# DM1098OAKW_Power_Supply.net
KiCad netlist of a schematic drawn in Altium Designer
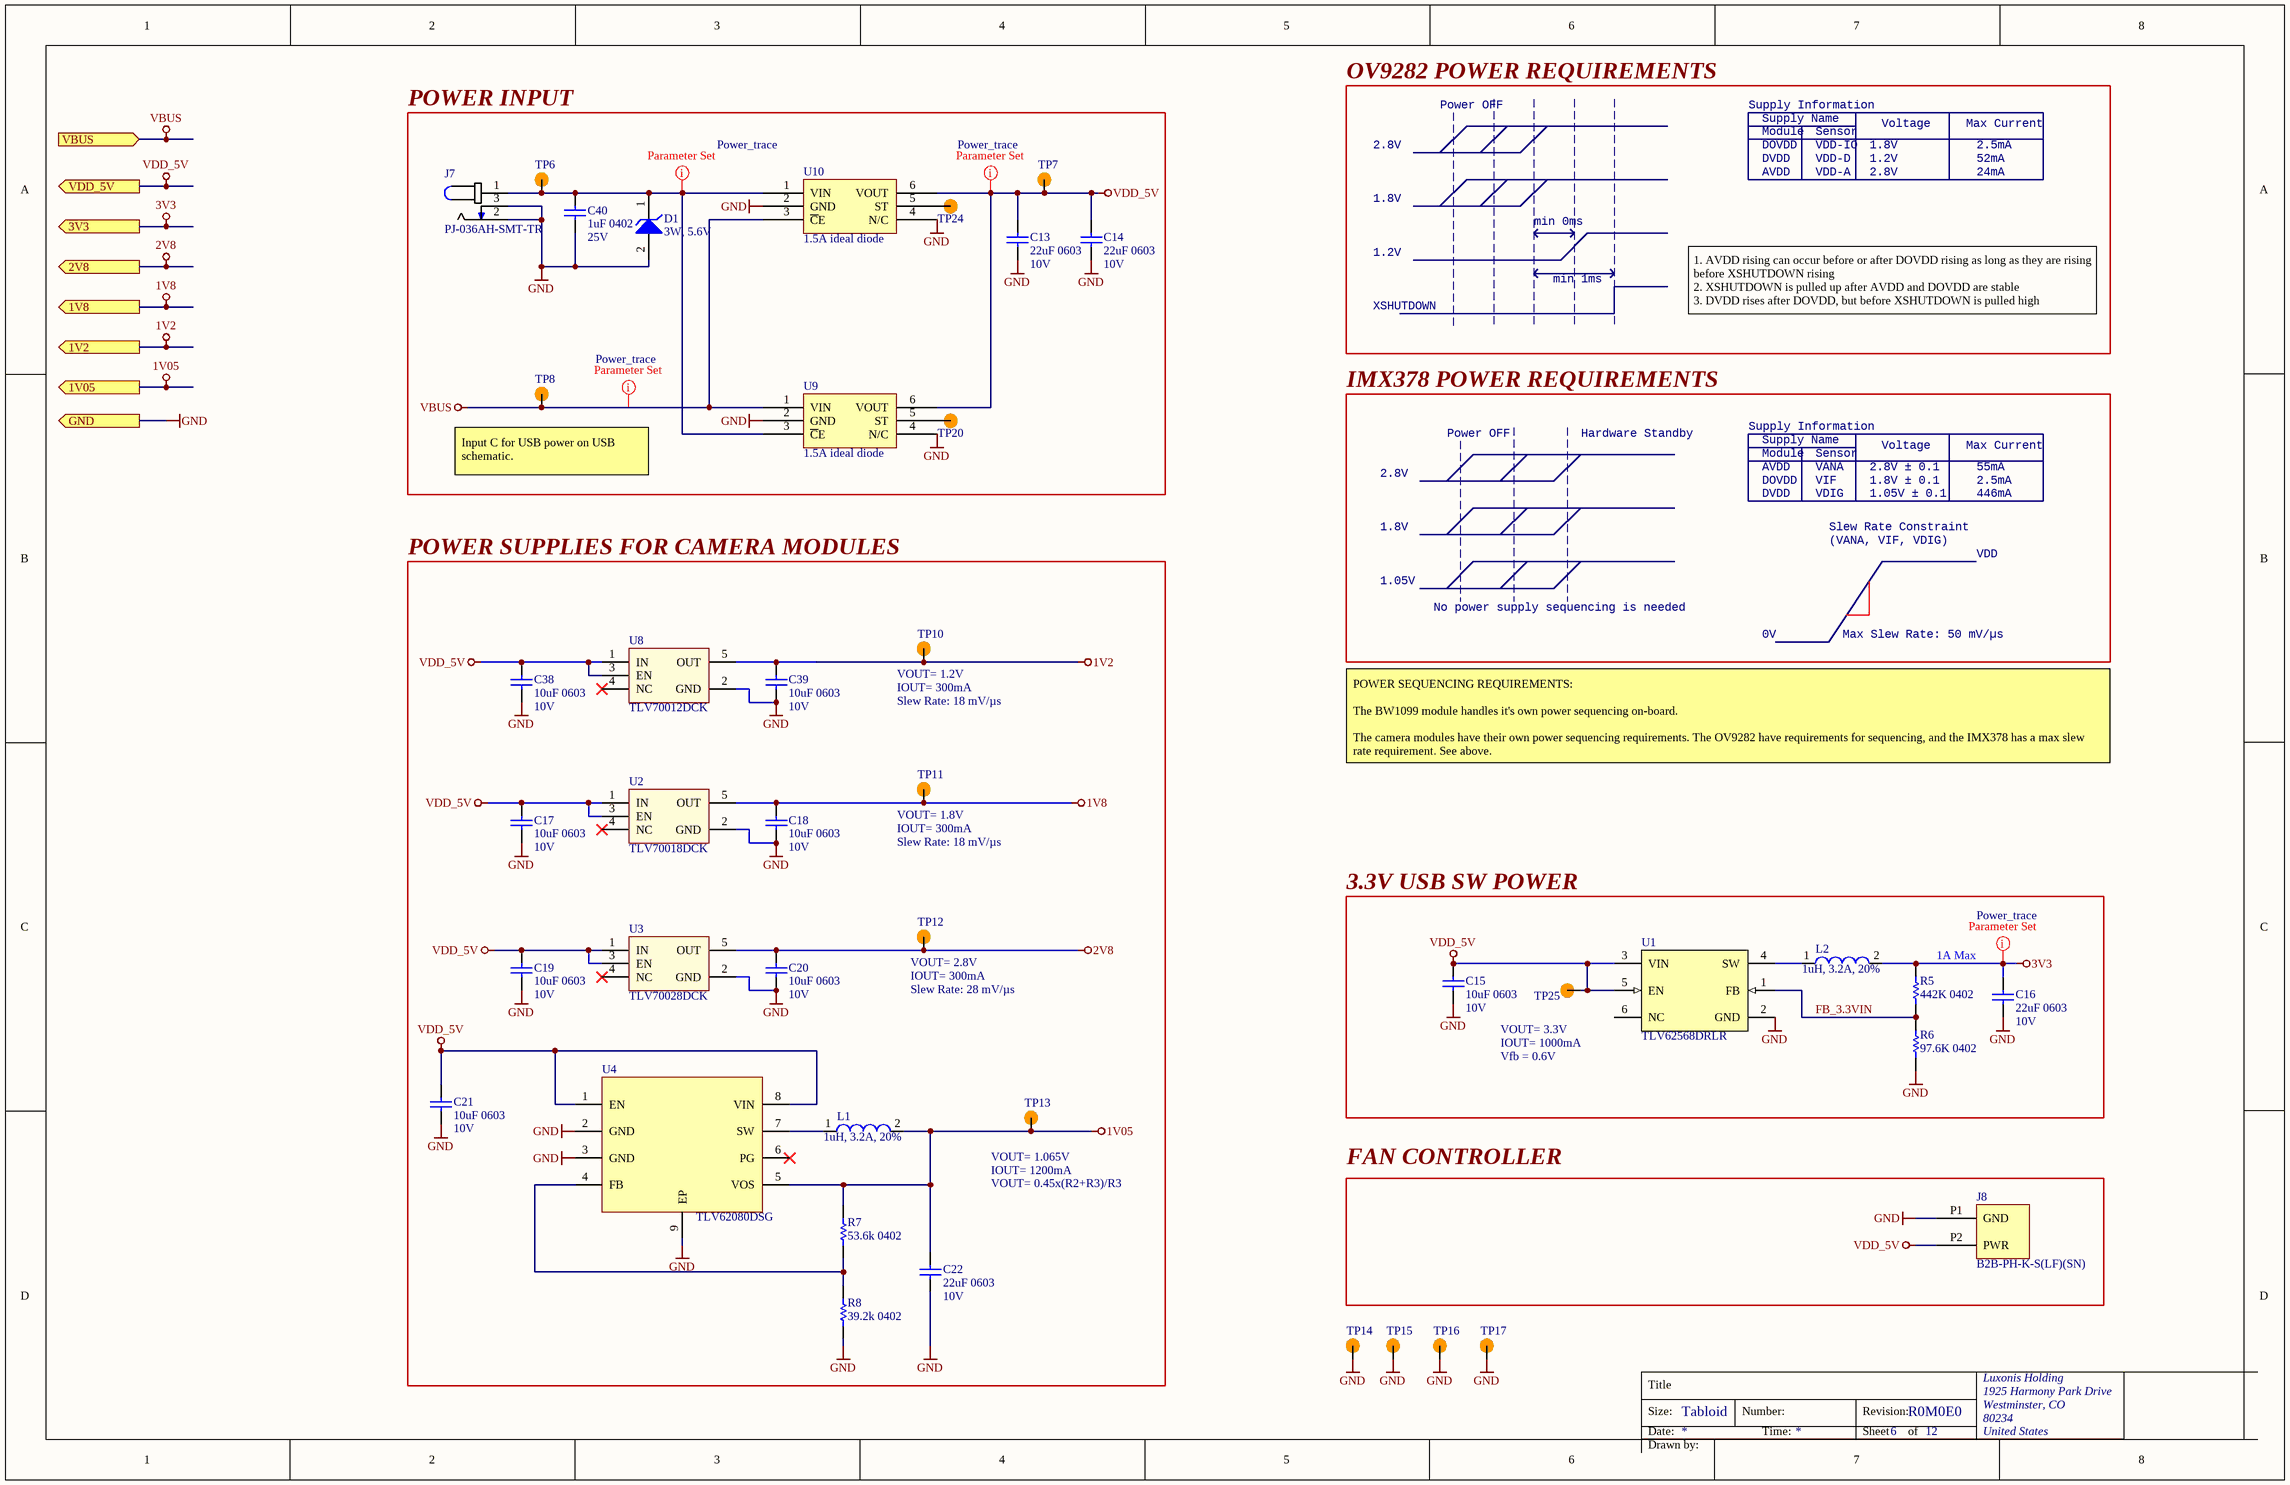
[diagram p0: DM1098OAKW_Power_Supply.SchDoc]

(export (version "E")
  (design (tool "Eeschema 10.0.6"))
  (components
    (comp (ref "C13")
      (value "22uF 0603")
      (footprint "CAP_Altium_Vault_Generic:CAPC0603(1608)100_L")
      (description "CAP CER 22UF 10V X5R 0603 20%")
      (fields (field (name "TOLERANCE") "20%") (field (name "VOLTAGE RATING") "10V"))
      (libsource (lib "LuxonisMaster") (part "GRM188R61A226ME15D"))
    )
    (comp (ref "C14")
      (value "22uF 0603")
      (footprint "CAP_Altium_Vault_Generic:CAPC0603(1608)100_L")
      (description "CAP CER 22UF 10V X5R 0603 20%")
      (fields (field (name "TOLERANCE") "20%") (field (name "VOLTAGE RATING") "10V"))
      (libsource (lib "LuxonisMaster") (part "GRM188R61A226ME15D"))
    )
    (comp (ref "C15")
      (value "10uF 0603")
      (footprint "CAP_Altium_Vault_Generic:CAPC0603(1608)100_L")
      (description "CAP CER 10UF 10V X5R 0603 20%")
      (fields (field (name "TOLERANCE") "20%") (field (name "VOLTAGE RATING") "10V"))
      (libsource (lib "LuxonisMaster") (part "GRM188R61A106ME69D"))
    )
    (comp (ref "C16")
      (value "22uF 0603")
      (footprint "CAP_Altium_Vault_Generic:CAPC0603(1608)100_N")
      (description "CAP CER 22UF 10V X5R 0603 20%")
      (fields (field (name "TOLERANCE") "20%") (field (name "VOLTAGE RATING") "10V"))
      (libsource (lib "LuxonisMaster") (part "GRM188R61A226ME15D"))
    )
    (comp (ref "C17")
      (value "10uF 0603")
      (footprint "CAP_Altium_Vault_Generic:CAPC0603(1608)100_L")
      (description "CAP CER 10UF 10V X5R 0603 20%")
      (fields (field (name "TOLERANCE") "20%") (field (name "VOLTAGE RATING") "10V"))
      (libsource (lib "LuxonisMaster") (part "GRM188R61A106ME69D"))
    )
    (comp (ref "C18")
      (value "10uF 0603")
      (footprint "CAP_Altium_Vault_Generic:CAPC0603(1608)100_L")
      (description "CAP CER 10UF 10V X5R 0603 20%")
      (fields (field (name "TOLERANCE") "20%") (field (name "VOLTAGE RATING") "10V"))
      (libsource (lib "LuxonisMaster") (part "GRM188R61A106ME69D"))
    )
    (comp (ref "C19")
      (value "10uF 0603")
      (footprint "CAP_Altium_Vault_Generic:CAPC0603(1608)100_L")
      (description "CAP CER 10UF 10V X5R 0603 20%")
      (fields (field (name "TOLERANCE") "20%") (field (name "VOLTAGE RATING") "10V"))
      (libsource (lib "LuxonisMaster") (part "GRM188R61A106ME69D"))
    )
    (comp (ref "C20")
      (value "10uF 0603")
      (footprint "CAP_Altium_Vault_Generic:CAPC0603(1608)100_L")
      (description "CAP CER 10UF 10V X5R 0603 20%")
      (fields (field (name "TOLERANCE") "20%") (field (name "VOLTAGE RATING") "10V"))
      (libsource (lib "LuxonisMaster") (part "GRM188R61A106ME69D"))
    )
    (comp (ref "C21")
      (value "10uF 0603")
      (footprint "CAP_Altium_Vault_Generic:CAPC0603(1608)100_L")
      (description "CAP CER 10UF 10V X5R 0603 20%")
      (fields (field (name "TOLERANCE") "20%") (field (name "VOLTAGE RATING") "10V"))
      (libsource (lib "LuxonisMaster") (part "GRM188R61A106ME69D"))
    )
    (comp (ref "C22")
      (value "22uF 0603")
      (footprint "CAP_Altium_Vault_Generic:CAPC0603(1608)100_L")
      (description "CAP CER 22UF 10V X5R 0603 20%")
      (fields (field (name "TOLERANCE") "20%") (field (name "VOLTAGE RATING") "10V"))
      (libsource (lib "LuxonisMaster") (part "GRM188R61A226ME15D"))
    )
    (comp (ref "C38")
      (value "10uF 0603")
      (footprint "CAP_Altium_Vault_Generic:CAPC0603(1608)100_L")
      (description "CAP CER 10UF 10V X5R 0603 20%")
      (fields (field (name "TOLERANCE") "20%") (field (name "VOLTAGE RATING") "10V"))
      (libsource (lib "LuxonisMaster") (part "GRM188R61A106ME69D"))
    )
    (comp (ref "C39")
      (value "10uF 0603")
      (footprint "CAP_Altium_Vault_Generic:CAPC0603(1608)100_L")
      (description "CAP CER 10UF 10V X5R 0603 20%")
      (fields (field (name "TOLERANCE") "20%") (field (name "VOLTAGE RATING") "10V"))
      (libsource (lib "LuxonisMaster") (part "GRM188R61A106ME69D"))
    )
    (comp (ref "C40")
      (value "1uF 0402")
      (footprint "CAP_Altium_Vault_Generic:CAPC0402(1005)70_L")
      (description "CAP CER 1UF 25V X5R 0402 10%")
      (fields
        (field (name "TOLERANCE") "10%")
        (field (name "VOLTAGE") "25V")
        (field (name "VOLTAGE RATING") "25V")
      )
      (libsource (lib "LuxonisMaster") (part "GRM155R61E105KA12D"))
    )
    (comp (ref "D1")
      (value "3W, 5.6V")
      (footprint "DM1092_R0M0E0:1SMB5919BT3G")
      (description "DIODE ZENER 5.6V 3W SMB")
      (fields (field (name "TOLERANCE") "5%"))
      (libsource (lib "DM1092_R0M0E0") (part "1SMB5919BT3G"))
    )
    (comp (ref "J7")
      (value "PJ-036AH-SMT-TR")
      (footprint "LuxonisMaster:PJ-036AH-SMT")
      (description "CONN PWR JACK 2X5.5MM SOLDER")
      (libsource (lib "LuxonisMaster") (part "PJ-036AH-SMT-TR"))
    )
    (comp (ref "J8")
      (value "B2B-PH-K-S(LF)(SN)")
      (footprint "LuxonisMaster:B2B-PH-K-S(LF)(SN)")
      (description "CONN HEADER VERT 2POS 2MM")
      (fields (field (name "MANUFACTURER") "JST"))
      (libsource (lib "LuxonisMaster") (part "B2B-PH-K-S(LF)(SN)"))
    )
    (comp (ref "L1")
      (value "1uH, 3.2A, 20%")
      (footprint "LuxonisMaster:DFE252012P-1R0M=P2")
      (description "FIXED IND 1UH 3.2A 42 MOHM SMD")
      (fields
        (field (name "MANUFACTURER") "Murata")
        (field (name "MANUFACTURER PART NUMBER") "DFE252012P-1R0M=P2")
      )
      (libsource (lib "LuxonisMaster") (part "DFE252012P-1R0M=P2"))
    )
    (comp (ref "L2")
      (value "1uH, 3.2A, 20%")
      (footprint "LuxonisMaster:DFE252012P-1R0M=P2")
      (description "FIXED IND 1UH 3.2A 42 MOHM SMD")
      (fields
        (field (name "MANUFACTURER") "Murata")
        (field (name "MANUFACTURER PART NUMBER") "DFE252012P-1R0M=P2")
      )
      (libsource (lib "LuxonisMaster") (part "DFE252012P-1R0M=P2"))
    )
    (comp (ref "R5")
      (value "442K 0402")
      (footprint "RES_Altium_Vault_Generic:RESC0402(1005)_N")
      (description "RES SMD 442K OHM 1% 1/16W 0402")
      (fields (field (name "TOLERANCE") "1%"))
      (libsource (lib "BW1092_R0M0E0") (part "CRCW0402442KFKED"))
    )
    (comp (ref "R6")
      (value "97.6K 0402")
      (footprint "RES_Altium_Vault_Generic:RESC0402(1005)_N")
      (description "RES SMD 97.6K OHM 1% 1/16W 0402")
      (fields (field (name "TOLERANCE") "1%"))
      (libsource (lib "BW1092_R0M0E0") (part "CRCW040297K6FKED"))
    )
    (comp (ref "R7")
      (value "53.6k 0402")
      (footprint "RES_Altium_Vault_Generic:RESC0402(1005)_L")
      (description "RES SMD 53.6K OHM 1% 1/16W 0402")
      (fields (field (name "TOLERANCE") "1%"))
      (libsource (lib "LuxonisMaster") (part "CRCW040253K6FKED"))
    )
    (comp (ref "R8")
      (value "39.2k 0402")
      (footprint "RES_Altium_Vault_Generic:RESC0402(1005)_L")
      (description "RES SMD 39.2K OHM 1% 1/16W 0402")
      (fields (field (name "TOLERANCE") "1%"))
      (libsource (lib "LuxonisMaster") (part "CRCW040239K2FKED"))
    )
    (comp (ref "TP6")
      (value "TP100_200_NS")
      (footprint "LuxonisMaster:TP100_200_NS")
      (libsource (lib "LuxonisMaster") (part "TEST_POINT"))
    )
    (comp (ref "TP7")
      (value "TP100_200_NS")
      (footprint "LuxonisMaster:TP100_200_NS")
      (libsource (lib "LuxonisMaster") (part "TEST_POINT"))
    )
    (comp (ref "TP8")
      (value "TP100_200_NS")
      (footprint "LuxonisMaster:TP100_200_NS")
      (libsource (lib "LuxonisMaster") (part "TEST_POINT"))
    )
    (comp (ref "TP10")
      (value "TP100_200_NS")
      (footprint "LuxonisMaster:TP100_200_NS")
      (libsource (lib "LuxonisMaster") (part "TEST_POINT"))
    )
    (comp (ref "TP11")
      (value "TP100_200_NS")
      (footprint "LuxonisMaster:TP100_200_NS")
      (libsource (lib "LuxonisMaster") (part "TEST_POINT"))
    )
    (comp (ref "TP12")
      (value "TP100_200_NS")
      (footprint "LuxonisMaster:TP100_200_NS")
      (libsource (lib "LuxonisMaster") (part "TEST_POINT"))
    )
    (comp (ref "TP13")
      (value "TP100_200_NS")
      (footprint "LuxonisMaster:TP100_200_NS")
      (libsource (lib "LuxonisMaster") (part "TEST_POINT"))
    )
    (comp (ref "TP14")
      (value "TP100_200_NS")
      (footprint "LuxonisMaster:TP100_200_NS")
      (libsource (lib "LuxonisMaster") (part "TEST_POINT"))
    )
    (comp (ref "TP15")
      (value "TP100_200_NS")
      (footprint "LuxonisMaster:TP100_200_NS")
      (libsource (lib "LuxonisMaster") (part "TEST_POINT"))
    )
    (comp (ref "TP16")
      (value "TP100_200_NS")
      (footprint "LuxonisMaster:TP100_200_NS")
      (libsource (lib "LuxonisMaster") (part "TEST_POINT"))
    )
    (comp (ref "TP17")
      (value "TP100_200_NS")
      (footprint "LuxonisMaster:TP100_200_NS")
      (libsource (lib "LuxonisMaster") (part "TEST_POINT"))
    )
    (comp (ref "TP20")
      (value "TP100_200_NS")
      (footprint "LuxonisMaster:TP100_200_NS")
      (libsource (lib "LuxonisMaster") (part "TEST_POINT"))
    )
    (comp (ref "TP24")
      (value "TP100_200_NS")
      (footprint "LuxonisMaster:TP100_200_NS")
      (libsource (lib "LuxonisMaster") (part "TEST_POINT"))
    )
    (comp (ref "TP25")
      (value "TP100_200_NS")
      (footprint "LuxonisMaster:TP100_200_NS")
      (libsource (lib "LuxonisMaster") (part "TEST_POINT"))
    )
    (comp (ref "U1")
      (value "TLV62568DRLR")
      (footprint "BW1092_R0M0E0:TLV62568DRLR")
      (description "IC REG BUCK ADJ 1A SOT563-6")
      (libsource (lib "BW1092_R0M0E0") (part "TLV62568DRLR"))
    )
    (comp (ref "U2")
      (value "TLV70018DCK")
      (footprint "LuxonisMaster:TLV70018DCK")
      (description "IC REG LINEAR 1.8V 200MA SC70-5 Linear Voltage Regulator IC  1 Output  200mA SC-70-5")
      (libsource (lib "LuxonisMaster") (part "TLV70018DCK"))
    )
    (comp (ref "U3")
      (value "TLV70028DCK")
      (footprint "LuxonisMaster:TLV70028DCK")
      (description "IC REG LINEAR 2.8V 200MA SC70-5 Linear Voltage Regulator IC  1 Output  200mA SC-70-5")
      (libsource (lib "LuxonisMaster") (part "TLV70028DCK"))
    )
    (comp (ref "U4")
      (value "TLV62080DSG")
      (footprint "LuxonisMaster:TLV62080DSG")
      (description "IC REG BUCK ADJ 1.2A SYNC 8WSON")
      (libsource (lib "LuxonisMaster") (part "TLV62080DSG"))
    )
    (comp (ref "U8")
      (value "TLV70012DCK")
      (footprint "LuxonisMaster:TLV70012DCK")
      (description "IC REG LINEAR 1.2V 200MA SC70-5")
      (libsource (lib "LuxonisMaster") (part "TLV70012DCK"))
    )
    (comp (ref "U9")
      (value "1.5A ideal diode")
      (footprint "BW1098OBC_R2M0E2:LM66100DCKR")
      (description "IC OR CTRLR IDEAL DIODE SC70-6")
      (libsource (lib "BW1098OBC_R2M0E2") (part "LM66100DCKR"))
    )
    (comp (ref "U10")
      (value "1.5A ideal diode")
      (footprint "BW1098OBC_R2M0E2:LM66100DCKR")
      (description "IC OR CTRLR IDEAL DIODE SC70-6")
      (libsource (lib "BW1098OBC_R2M0E2") (part "LM66100DCKR"))
    )
  )
  (nets
    (net (code "1") (name "/FB_3.3VIN") (class "Default")
      (node (ref "R5") (pin "1") (pinfunction "1_1") (pintype "passive"))
      (node (ref "R6") (pin "2") (pinfunction "2_2") (pintype "passive"))
      (node (ref "U1") (pin "1") (pinfunction "FB_1") (pintype "input"))
    )
    (net (code "2") (name "1V2") (class "Default")
      (node (ref "C39") (pin "2") (pinfunction "2_2") (pintype "passive"))
      (node (ref "TP10") (pin "1") (pintype "passive"))
      (node (ref "U8") (pin "5") (pinfunction "OUT_5") (pintype "passive"))
    )
    (net (code "3") (name "1V05") (class "Default")
      (node (ref "C22") (pin "2") (pinfunction "2_2") (pintype "passive"))
      (node (ref "L1") (pin "2") (pinfunction "2_2") (pintype "passive"))
      (node (ref "R7") (pin "2") (pinfunction "2_2") (pintype "passive"))
      (node (ref "TP13") (pin "1") (pintype "passive"))
      (node (ref "U4") (pin "5") (pinfunction "VOS_5") (pintype "passive"))
    )
    (net (code "4") (name "1V8") (class "Default")
      (node (ref "C18") (pin "2") (pinfunction "2_2") (pintype "passive"))
      (node (ref "TP11") (pin "1") (pintype "passive"))
      (node (ref "U2") (pin "5") (pinfunction "OUT_5") (pintype "passive"))
    )
    (net (code "5") (name "2V8") (class "Default")
      (node (ref "C20") (pin "2") (pinfunction "2_2") (pintype "passive"))
      (node (ref "TP12") (pin "1") (pintype "passive"))
      (node (ref "U3") (pin "5") (pinfunction "OUT_5") (pintype "passive"))
    )
    (net (code "6") (name "3V3") (class "Default")
      (node (ref "C16") (pin "1") (pinfunction "1_1") (pintype "passive"))
      (node (ref "L2") (pin "2") (pinfunction "2_2") (pintype "passive"))
      (node (ref "R5") (pin "2") (pinfunction "2_2") (pintype "passive"))
    )
    (net (code "7") (name "GND") (class "Default")
      (node (ref "C13") (pin "1") (pinfunction "1_1") (pintype "passive"))
      (node (ref "C14") (pin "1") (pinfunction "1_1") (pintype "passive"))
      (node (ref "C15") (pin "1") (pinfunction "1_1") (pintype "passive"))
      (node (ref "C16") (pin "2") (pinfunction "2_2") (pintype "passive"))
      (node (ref "C17") (pin "1") (pinfunction "1_1") (pintype "passive"))
      (node (ref "C18") (pin "1") (pinfunction "1_1") (pintype "passive"))
      (node (ref "C19") (pin "1") (pinfunction "1_1") (pintype "passive"))
      (node (ref "C20") (pin "1") (pinfunction "1_1") (pintype "passive"))
      (node (ref "C21") (pin "1") (pinfunction "1_1") (pintype "passive"))
      (node (ref "C22") (pin "1") (pinfunction "1_1") (pintype "passive"))
      (node (ref "C38") (pin "1") (pinfunction "1_1") (pintype "passive"))
      (node (ref "C39") (pin "1") (pinfunction "1_1") (pintype "passive"))
      (node (ref "C40") (pin "1") (pinfunction "1_1") (pintype "passive"))
      (node (ref "D1") (pin "2") (pinfunction "A_2") (pintype "passive"))
      (node (ref "J7") (pin "2") (pinfunction "2_2") (pintype "passive"))
      (node (ref "J7") (pin "3") (pinfunction "3_3") (pintype "passive"))
      (node (ref "J8") (pin "P1") (pinfunction "GND_P1") (pintype "passive"))
      (node (ref "R6") (pin "1") (pinfunction "1_1") (pintype "passive"))
      (node (ref "R8") (pin "1") (pinfunction "1_1") (pintype "passive"))
      (node (ref "TP14") (pin "1") (pintype "passive"))
      (node (ref "TP15") (pin "1") (pintype "passive"))
      (node (ref "TP16") (pin "1") (pintype "passive"))
      (node (ref "TP17") (pin "1") (pintype "passive"))
      (node (ref "U1") (pin "2") (pinfunction "GND_2") (pintype "power_in"))
      (node (ref "U10") (pin "2") (pinfunction "GND_2") (pintype "passive"))
      (node (ref "U10") (pin "4") (pinfunction "N/C_4") (pintype "passive"))
      (node (ref "U2") (pin "2") (pinfunction "GND_2") (pintype "passive"))
      (node (ref "U3") (pin "2") (pinfunction "GND_2") (pintype "passive"))
      (node (ref "U4") (pin "2") (pinfunction "GND_2") (pintype "passive"))
      (node (ref "U4") (pin "3") (pinfunction "GND_3") (pintype "passive"))
      (node (ref "U4") (pin "9") (pinfunction "EP_9") (pintype "passive"))
      (node (ref "U8") (pin "2") (pinfunction "GND_2") (pintype "passive"))
      (node (ref "U9") (pin "2") (pinfunction "GND_2") (pintype "passive"))
      (node (ref "U9") (pin "4") (pinfunction "N/C_4") (pintype "passive"))
    )
    (net (code "8") (name "Net-(D1-K)") (class "Default")
      (node (ref "C40") (pin "2") (pinfunction "2_2") (pintype "passive"))
      (node (ref "D1") (pin "1") (pinfunction "K_1") (pintype "passive"))
      (node (ref "J7") (pin "1") (pinfunction "1_1") (pintype "passive"))
      (node (ref "TP6") (pin "1") (pintype "passive"))
      (node (ref "U10") (pin "1") (pinfunction "VIN_1") (pintype "passive"))
      (node (ref "U9") (pin "3") (pinfunction "~{C}E_3") (pintype "passive"))
    )
    (net (code "9") (name "Net-(U1-SW)") (class "Default")
      (node (ref "L2") (pin "1") (pinfunction "1_1") (pintype "passive"))
      (node (ref "U1") (pin "4") (pinfunction "SW_4") (pintype "power_in"))
    )
    (net (code "10") (name "Net-(U4-FB)") (class "Default")
      (node (ref "R7") (pin "1") (pinfunction "1_1") (pintype "passive"))
      (node (ref "R8") (pin "2") (pinfunction "2_2") (pintype "passive"))
      (node (ref "U4") (pin "4") (pinfunction "FB_4") (pintype "passive"))
    )
    (net (code "11") (name "Net-(U4-SW)") (class "Default")
      (node (ref "L1") (pin "1") (pinfunction "1_1") (pintype "passive"))
      (node (ref "U4") (pin "7") (pinfunction "SW_7") (pintype "passive"))
    )
    (net (code "12") (name "Net-(U9-ST)") (class "Default")
      (node (ref "TP20") (pin "1") (pintype "passive"))
      (node (ref "U9") (pin "5") (pinfunction "ST_5") (pintype "passive"))
    )
    (net (code "13") (name "Net-(U10-ST)") (class "Default")
      (node (ref "TP24") (pin "1") (pintype "passive"))
      (node (ref "U10") (pin "5") (pinfunction "ST_5") (pintype "passive"))
    )
    (net (code "14") (name "VBUS") (class "Default")
      (node (ref "TP8") (pin "1") (pintype "passive"))
      (node (ref "U10") (pin "3") (pinfunction "~{C}E_3") (pintype "passive"))
      (node (ref "U9") (pin "1") (pinfunction "VIN_1") (pintype "passive"))
    )
    (net (code "15") (name "VDD_5V") (class "Default")
      (node (ref "C13") (pin "2") (pinfunction "2_2") (pintype "passive"))
      (node (ref "C14") (pin "2") (pinfunction "2_2") (pintype "passive"))
      (node (ref "C15") (pin "2") (pinfunction "2_2") (pintype "passive"))
      (node (ref "C17") (pin "2") (pinfunction "2_2") (pintype "passive"))
      (node (ref "C19") (pin "2") (pinfunction "2_2") (pintype "passive"))
      (node (ref "C21") (pin "2") (pinfunction "2_2") (pintype "passive"))
      (node (ref "C38") (pin "2") (pinfunction "2_2") (pintype "passive"))
      (node (ref "J8") (pin "P2") (pinfunction "PWR_P2") (pintype "passive"))
      (node (ref "TP25") (pin "1") (pintype "passive"))
      (node (ref "TP7") (pin "1") (pintype "passive"))
      (node (ref "U1") (pin "3") (pinfunction "VIN_3") (pintype "power_in"))
      (node (ref "U1") (pin "5") (pinfunction "EN_5") (pintype "input"))
      (node (ref "U10") (pin "6") (pinfunction "VOUT_6") (pintype "passive"))
      (node (ref "U2") (pin "1") (pinfunction "IN_1") (pintype "passive"))
      (node (ref "U2") (pin "3") (pinfunction "EN_3") (pintype "passive"))
      (node (ref "U3") (pin "1") (pinfunction "IN_1") (pintype "passive"))
      (node (ref "U3") (pin "3") (pinfunction "EN_3") (pintype "passive"))
      (node (ref "U4") (pin "1") (pinfunction "EN_1") (pintype "passive"))
      (node (ref "U4") (pin "8") (pinfunction "VIN_8") (pintype "passive"))
      (node (ref "U8") (pin "1") (pinfunction "IN_1") (pintype "passive"))
      (node (ref "U8") (pin "3") (pinfunction "EN_3") (pintype "passive"))
      (node (ref "U9") (pin "6") (pinfunction "VOUT_6") (pintype "passive"))
    )
    (net (code "16") (name "unconnected-(U1-NC-Pad6)") (class "Default")
      (node (ref "U1") (pin "6") (pinfunction "NC_6") (pintype "passive"))
    )
    (net (code "17") (name "unconnected-(U2-NC-Pad4)") (class "Default")
      (node (ref "U2") (pin "4") (pinfunction "NC_4") (pintype "passive+no_connect"))
    )
    (net (code "18") (name "unconnected-(U3-NC-Pad4)") (class "Default")
      (node (ref "U3") (pin "4") (pinfunction "NC_4") (pintype "passive+no_connect"))
    )
    (net (code "19") (name "unconnected-(U4-PG-Pad6)") (class "Default")
      (node (ref "U4") (pin "6") (pinfunction "PG_6") (pintype "passive+no_connect"))
    )
    (net (code "20") (name "unconnected-(U8-NC-Pad4)") (class "Default")
      (node (ref "U8") (pin "4") (pinfunction "NC_4") (pintype "passive+no_connect"))
    )
  )
)
